# PIC.net
KiCad netlist of a schematic drawn in Altium Designer
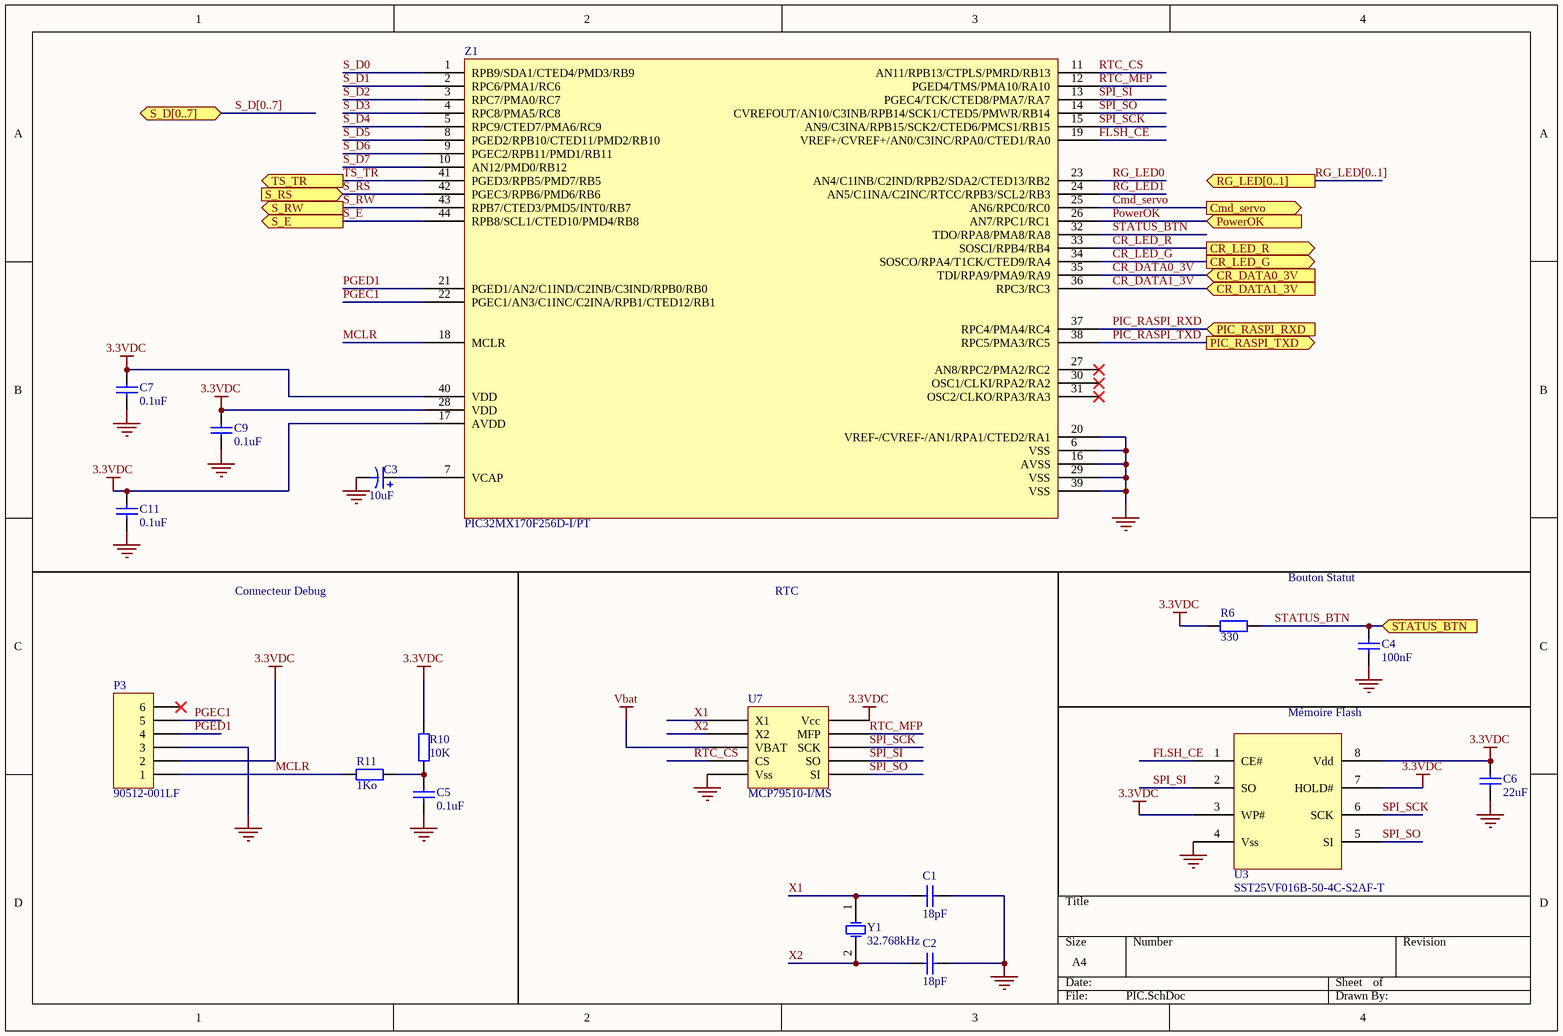
[diagram p0: PIC.SchDoc]

(export (version "E")
  (design (tool "Eeschema 10.0.6"))
  (components
    (comp (ref "C1")
      (value "18pF")
      (footprint "0603")
      (description "Capacitor")
      (libsource (lib "Miscellaneous Devices") (part "Cap"))
    )
    (comp (ref "C2")
      (value "18pF")
      (footprint "0603")
      (description "Capacitor")
      (libsource (lib "Miscellaneous Devices") (part "Cap"))
    )
    (comp (ref "C3")
      (value "10uF")
      (footprint "C3")
      (libsource (lib "Miscellaneous Devices") (part "Cap Pol1"))
    )
    (comp (ref "C4")
      (value "100nF")
      (footprint "0603")
      (description "Capacitor")
      (libsource (lib "Miscellaneous Devices") (part "Cap"))
    )
    (comp (ref "C5")
      (value "0.1uF")
      (footprint "0603")
      (description "Capacitor")
      (libsource (lib "Miscellaneous Devices") (part "Cap"))
    )
    (comp (ref "C6")
      (value "22uF")
      (footprint "0603")
      (description "Cout_Reg_3.3v")
      (libsource (lib "Miscellaneous Devices") (part "Cap"))
    )
    (comp (ref "C7")
      (value "0.1uF")
      (footprint "0603")
      (description "Capacitor")
      (libsource (lib "Miscellaneous Devices") (part "Cap"))
    )
    (comp (ref "C9")
      (value "0.1uF")
      (footprint "0603")
      (description "Capacitor")
      (libsource (lib "Miscellaneous Devices") (part "Cap"))
    )
    (comp (ref "C11")
      (value "0.1uF")
      (footprint "0603")
      (description "Capacitor")
      (libsource (lib "Miscellaneous Devices") (part "Cap"))
    )
    (comp (ref "P3")
      (value "90512-001LF")
      (footprint "RJ12")
      (description "PortRJ12_debug")
      (libsource (lib "Miscellaneous Connectors") (part "Header 6"))
    )
    (comp (ref "R6")
      (value "330")
      (footprint "0603")
      (description "Resistor")
      (libsource (lib "") (part "Res2_2"))
    )
    (comp (ref "R10")
      (value "10K")
      (footprint "0603")
      (description "Resistor")
      (libsource (lib "") (part "Res2_1"))
    )
    (comp (ref "R11")
      (value "1Ko")
      (footprint "0603")
      (description "Resistor")
      (libsource (lib "Miscellaneous Devices") (part "Res2"))
    )
    (comp (ref "U3")
      (value "SST25VF016B-50-4C-S2AF-T")
      (footprint "FLASH")
      (description "FLASH")
      (libsource (lib "Schlib1") (part "Memoire"))
    )
    (comp (ref "U7")
      (value "MCP79510-I/MS")
      (footprint "rtc")
      (description "RTC")
      (libsource (lib "Schlib1") (part "MCP79510"))
    )
    (comp (ref "Y1")
      (value "32.768kHz")
      (footprint "QUARTZ32KHz")
      (description "Crystal Oscillator")
      (libsource (lib "Miscellaneous Devices") (part "XTAL"))
    )
    (comp (ref "Z1")
      (value "PIC32MX170F256D-I/PT")
      (footprint "TQFP-44_L")
      (description "PIC")
      (libsource (lib "Schlib1") (part "PIC32_1"))
    )
  )
  (nets
    (net (code "1") (name "/CR_DATA0_3V") (class "Default")
      (node (ref "Z1") (pin "35") (pinfunction "TDI/RPA9/PMA9/RA9_35") (pintype "passive"))
    )
    (net (code "2") (name "/CR_DATA1_3V") (class "Default")
      (node (ref "Z1") (pin "36") (pinfunction "RPC3/RC3_36") (pintype "passive"))
    )
    (net (code "3") (name "/CR_LED_G") (class "Default")
      (node (ref "Z1") (pin "34") (pinfunction "SOSCO/RPA4/T1CK/CTED9/RA4_34") (pintype "passive"))
    )
    (net (code "4") (name "/CR_LED_R") (class "Default")
      (node (ref "Z1") (pin "33") (pinfunction "SOSCI/RPB4/RB4_33") (pintype "passive"))
    )
    (net (code "5") (name "/Cmd_servo") (class "Default")
      (node (ref "Z1") (pin "25") (pinfunction "AN6/RPC0/RC0_25") (pintype "passive"))
    )
    (net (code "6") (name "/FLSH_CE") (class "Default")
      (node (ref "U3") (pin "1") (pinfunction "CE#_1") (pintype "passive"))
      (node (ref "Z1") (pin "19") (pinfunction "VREF+/CVREF+/AN0/C3INC/RPA0/CTED1/RA0_19") (pintype "passive"))
    )
    (net (code "7") (name "/MCLR") (class "Default")
      (node (ref "P3") (pin "1") (pinfunction "1_1") (pintype "passive"))
      (node (ref "R11") (pin "2") (pinfunction "2_2") (pintype "passive"))
      (node (ref "Z1") (pin "18") (pinfunction "MCLR_18") (pintype "passive"))
    )
    (net (code "8") (name "/PGEC1") (class "Default")
      (node (ref "P3") (pin "5") (pinfunction "5_5") (pintype "passive"))
      (node (ref "Z1") (pin "22") (pinfunction "PGEC1/AN3/C1INC/C2INA/RPB1/CTED12/RB1_22") (pintype "passive"))
    )
    (net (code "9") (name "/PGED1") (class "Default")
      (node (ref "P3") (pin "4") (pinfunction "4_4") (pintype "passive"))
      (node (ref "Z1") (pin "21") (pinfunction "PGED1/AN2/C1IND/C2INB/C3IND/RPB0/RB0_21") (pintype "passive"))
    )
    (net (code "10") (name "/PIC_RASPI_RXD") (class "Default")
      (node (ref "Z1") (pin "37") (pinfunction "RPC4/PMA4/RC4_37") (pintype "passive"))
    )
    (net (code "11") (name "/PIC_RASPI_TXD") (class "Default")
      (node (ref "Z1") (pin "38") (pinfunction "RPC5/PMA3/RC5_38") (pintype "passive"))
    )
    (net (code "12") (name "/PowerOK") (class "Default")
      (node (ref "Z1") (pin "26") (pinfunction "AN7/RPC1/RC1_26") (pintype "passive"))
    )
    (net (code "13") (name "/RG_LED0") (class "Default")
      (node (ref "Z1") (pin "23") (pinfunction "AN4/C1INB/C2IND/RPB2/SDA2/CTED13/RB2_23") (pintype "passive"))
    )
    (net (code "14") (name "/RG_LED1") (class "Default")
      (node (ref "Z1") (pin "24") (pinfunction "AN5/C1INA/C2INC/RTCC/RPB3/SCL2/RB3_24") (pintype "passive"))
    )
    (net (code "16") (name "/RTC_CS") (class "Default")
      (node (ref "U7") (pin "4") (pinfunction "CS_4") (pintype "passive"))
      (node (ref "Z1") (pin "11") (pinfunction "AN11/RPB13/CTPLS/PMRD/RB13_11") (pintype "passive"))
    )
    (net (code "17") (name "/RTC_MFP") (class "Default")
      (node (ref "U7") (pin "9") (pinfunction "MFP_9") (pintype "passive"))
      (node (ref "Z1") (pin "12") (pinfunction "PGED4/TMS/PMA10/RA10_12") (pintype "passive"))
    )
    (net (code "18") (name "/SPI_SCK") (class "Default")
      (node (ref "U3") (pin "6") (pinfunction "SCK_6") (pintype "passive"))
      (node (ref "U7") (pin "8") (pinfunction "SCK_8") (pintype "passive"))
      (node (ref "Z1") (pin "15") (pinfunction "AN9/C3INA/RPB15/SCK2/CTED6/PMCS1/RB15_15") (pintype "passive"))
    )
    (net (code "19") (name "/SPI_SI") (class "Default")
      (node (ref "U3") (pin "2") (pinfunction "SO_2") (pintype "passive"))
      (node (ref "U7") (pin "7") (pinfunction "SO_7") (pintype "passive"))
      (node (ref "Z1") (pin "13") (pinfunction "PGEC4/TCK/CTED8/PMA7/RA7_13") (pintype "passive"))
    )
    (net (code "20") (name "/SPI_SO") (class "Default")
      (node (ref "U3") (pin "5") (pinfunction "SI_5") (pintype "passive"))
      (node (ref "U7") (pin "6") (pinfunction "SI_6") (pintype "passive"))
      (node (ref "Z1") (pin "14") (pinfunction "CVREFOUT/AN10/C3INB/RPB14/SCK1/CTED5/PMWR/RB14_14") (pintype "passive"))
    )
    (net (code "21") (name "/STATUS_BTN") (class "Default")
      (node (ref "C4") (pin "2") (pinfunction "2_2") (pintype "passive"))
      (node (ref "R6") (pin "2") (pinfunction "2_2") (pintype "passive"))
      (node (ref "Z1") (pin "32") (pinfunction "TDO/RPA8/PMA8/RA8_32") (pintype "passive"))
    )
    (net (code "22") (name "/S_D0") (class "Default")
      (node (ref "Z1") (pin "1") (pinfunction "RPB9/SDA1/CTED4/PMD3/RB9_1") (pintype "passive"))
    )
    (net (code "23") (name "/S_D1") (class "Default")
      (node (ref "Z1") (pin "2") (pinfunction "RPC6/PMA1/RC6_2") (pintype "passive"))
    )
    (net (code "24") (name "/S_D2") (class "Default")
      (node (ref "Z1") (pin "3") (pinfunction "RPC7/PMA0/RC7_3") (pintype "passive"))
    )
    (net (code "25") (name "/S_D3") (class "Default")
      (node (ref "Z1") (pin "4") (pinfunction "RPC8/PMA5/RC8_4") (pintype "passive"))
    )
    (net (code "26") (name "/S_D4") (class "Default")
      (node (ref "Z1") (pin "5") (pinfunction "RPC9/CTED7/PMA6/RC9_5") (pintype "passive"))
    )
    (net (code "27") (name "/S_D5") (class "Default")
      (node (ref "Z1") (pin "8") (pinfunction "PGED2/RPB10/CTED11/PMD2/RB10_8") (pintype "passive"))
    )
    (net (code "28") (name "/S_D6") (class "Default")
      (node (ref "Z1") (pin "9") (pinfunction "PGEC2/RPB11/PMD1/RB11_9") (pintype "passive"))
    )
    (net (code "29") (name "/S_D7") (class "Default")
      (node (ref "Z1") (pin "10") (pinfunction "AN12/PMD0/RB12_10") (pintype "passive"))
    )
    (net (code "31") (name "/S_E") (class "Default")
      (node (ref "Z1") (pin "44") (pinfunction "RPB8/SCL1/CTED10/PMD4/RB8_44") (pintype "passive"))
    )
    (net (code "32") (name "/S_RS") (class "Default")
      (node (ref "Z1") (pin "42") (pinfunction "PGEC3/RPB6/PMD6/RB6_42") (pintype "passive"))
    )
    (net (code "33") (name "/S_RW") (class "Default")
      (node (ref "Z1") (pin "43") (pinfunction "RPB7/CTED3/PMD5/INT0/RB7_43") (pintype "passive"))
    )
    (net (code "34") (name "/TS_TR") (class "Default")
      (node (ref "Z1") (pin "41") (pinfunction "PGED3/RPB5/PMD7/RB5_41") (pintype "passive"))
    )
    (net (code "35") (name "/X1") (class "Default")
      (node (ref "C1") (pin "2") (pinfunction "2_2") (pintype "passive"))
      (node (ref "U7") (pin "1") (pinfunction "X1_1") (pintype "passive"))
      (node (ref "Y1") (pin "1") (pinfunction "OSC1_1") (pintype "passive"))
    )
    (net (code "36") (name "/X2") (class "Default")
      (node (ref "C2") (pin "2") (pinfunction "2_2") (pintype "passive"))
      (node (ref "U7") (pin "2") (pinfunction "X2_2") (pintype "passive"))
      (node (ref "Y1") (pin "2") (pinfunction "OSC2_2") (pintype "passive"))
    )
    (net (code "37") (name "3.3VDC") (class "Default")
      (node (ref "C11") (pin "1") (pinfunction "1_1") (pintype "passive"))
      (node (ref "C6") (pin "2") (pinfunction "2_2") (pintype "passive"))
      (node (ref "C7") (pin "1") (pinfunction "1_1") (pintype "passive"))
      (node (ref "C9") (pin "1") (pinfunction "1_1") (pintype "passive"))
      (node (ref "P3") (pin "2") (pinfunction "2_2") (pintype "passive"))
      (node (ref "R10") (pin "2") (pinfunction "2_2") (pintype "passive"))
      (node (ref "R6") (pin "1") (pinfunction "1_1") (pintype "passive"))
      (node (ref "U3") (pin "3") (pinfunction "WP#_3") (pintype "passive"))
      (node (ref "U3") (pin "7") (pinfunction "HOLD#_7") (pintype "passive"))
      (node (ref "U3") (pin "8") (pinfunction "Vdd_8") (pintype "passive"))
      (node (ref "U7") (pin "10") (pinfunction "Vcc_10") (pintype "passive"))
      (node (ref "Z1") (pin "17") (pinfunction "AVDD_17") (pintype "passive"))
      (node (ref "Z1") (pin "28") (pinfunction "VDD_28") (pintype "passive"))
      (node (ref "Z1") (pin "40") (pinfunction "VDD_40") (pintype "passive"))
    )
    (net (code "38") (name "GND") (class "Default")
      (node (ref "C1") (pin "1") (pinfunction "1_1") (pintype "passive"))
      (node (ref "C11") (pin "2") (pinfunction "2_2") (pintype "passive"))
      (node (ref "C2") (pin "1") (pinfunction "1_1") (pintype "passive"))
      (node (ref "C3") (pin "2") (pinfunction "2_2") (pintype "passive"))
      (node (ref "C4") (pin "1") (pinfunction "1_1") (pintype "passive"))
      (node (ref "C5") (pin "1") (pinfunction "1_1") (pintype "passive"))
      (node (ref "C6") (pin "1") (pinfunction "1_1") (pintype "passive"))
      (node (ref "C7") (pin "2") (pinfunction "2_2") (pintype "passive"))
      (node (ref "C9") (pin "2") (pinfunction "2_2") (pintype "passive"))
      (node (ref "P3") (pin "3") (pinfunction "3_3") (pintype "passive"))
      (node (ref "U3") (pin "4") (pinfunction "Vss_4") (pintype "passive"))
      (node (ref "U7") (pin "5") (pinfunction "Vss_5") (pintype "passive"))
      (node (ref "Z1") (pin "16") (pinfunction "AVSS_16") (pintype "passive"))
      (node (ref "Z1") (pin "20") (pinfunction "VREF-/CVREF-/AN1/RPA1/CTED2/RA1_20") (pintype "passive"))
      (node (ref "Z1") (pin "29") (pinfunction "VSS_29") (pintype "passive"))
      (node (ref "Z1") (pin "39") (pinfunction "VSS_39") (pintype "passive"))
      (node (ref "Z1") (pin "6") (pinfunction "VSS_6") (pintype "passive"))
    )
    (net (code "39") (name "Net-(C5-Pad2)") (class "Default")
      (node (ref "C5") (pin "2") (pinfunction "2_2") (pintype "passive"))
      (node (ref "R10") (pin "1") (pinfunction "1_1") (pintype "passive"))
      (node (ref "R11") (pin "1") (pinfunction "1_1") (pintype "passive"))
    )
    (net (code "40") (name "Net-(Z1-VCAP)") (class "Default")
      (node (ref "C3") (pin "1") (pinfunction "1_1") (pintype "passive"))
      (node (ref "Z1") (pin "7") (pinfunction "VCAP_7") (pintype "passive"))
    )
    (net (code "41") (name "Vbat") (class "Default")
      (node (ref "U7") (pin "3") (pinfunction "VBAT_3") (pintype "passive"))
    )
    (net (code "42") (name "unconnected-(P3-Pad6)") (class "Default")
      (node (ref "P3") (pin "6") (pinfunction "6_6") (pintype "passive+no_connect"))
    )
    (net (code "43") (name "unconnected-(Z1-AN8{slash}RPC2{slash}PMA2{slash}RC2-Pad27)") (class "Default")
      (node (ref "Z1") (pin "27") (pinfunction "AN8/RPC2/PMA2/RC2_27") (pintype "passive+no_connect"))
    )
    (net (code "44") (name "unconnected-(Z1-OSC1{slash}CLKI{slash}RPA2{slash}RA2-Pad30)") (class "Default")
      (node (ref "Z1") (pin "30") (pinfunction "OSC1/CLKI/RPA2/RA2_30") (pintype "passive+no_connect"))
    )
    (net (code "45") (name "unconnected-(Z1-OSC2{slash}CLKO{slash}RPA3{slash}RA3-Pad31)") (class "Default")
      (node (ref "Z1") (pin "31") (pinfunction "OSC2/CLKO/RPA3/RA3_31") (pintype "passive+no_connect"))
    )
  )
)
